# 64XkeySchem.net
KiCad netlist of a schematic drawn in Altium Designer
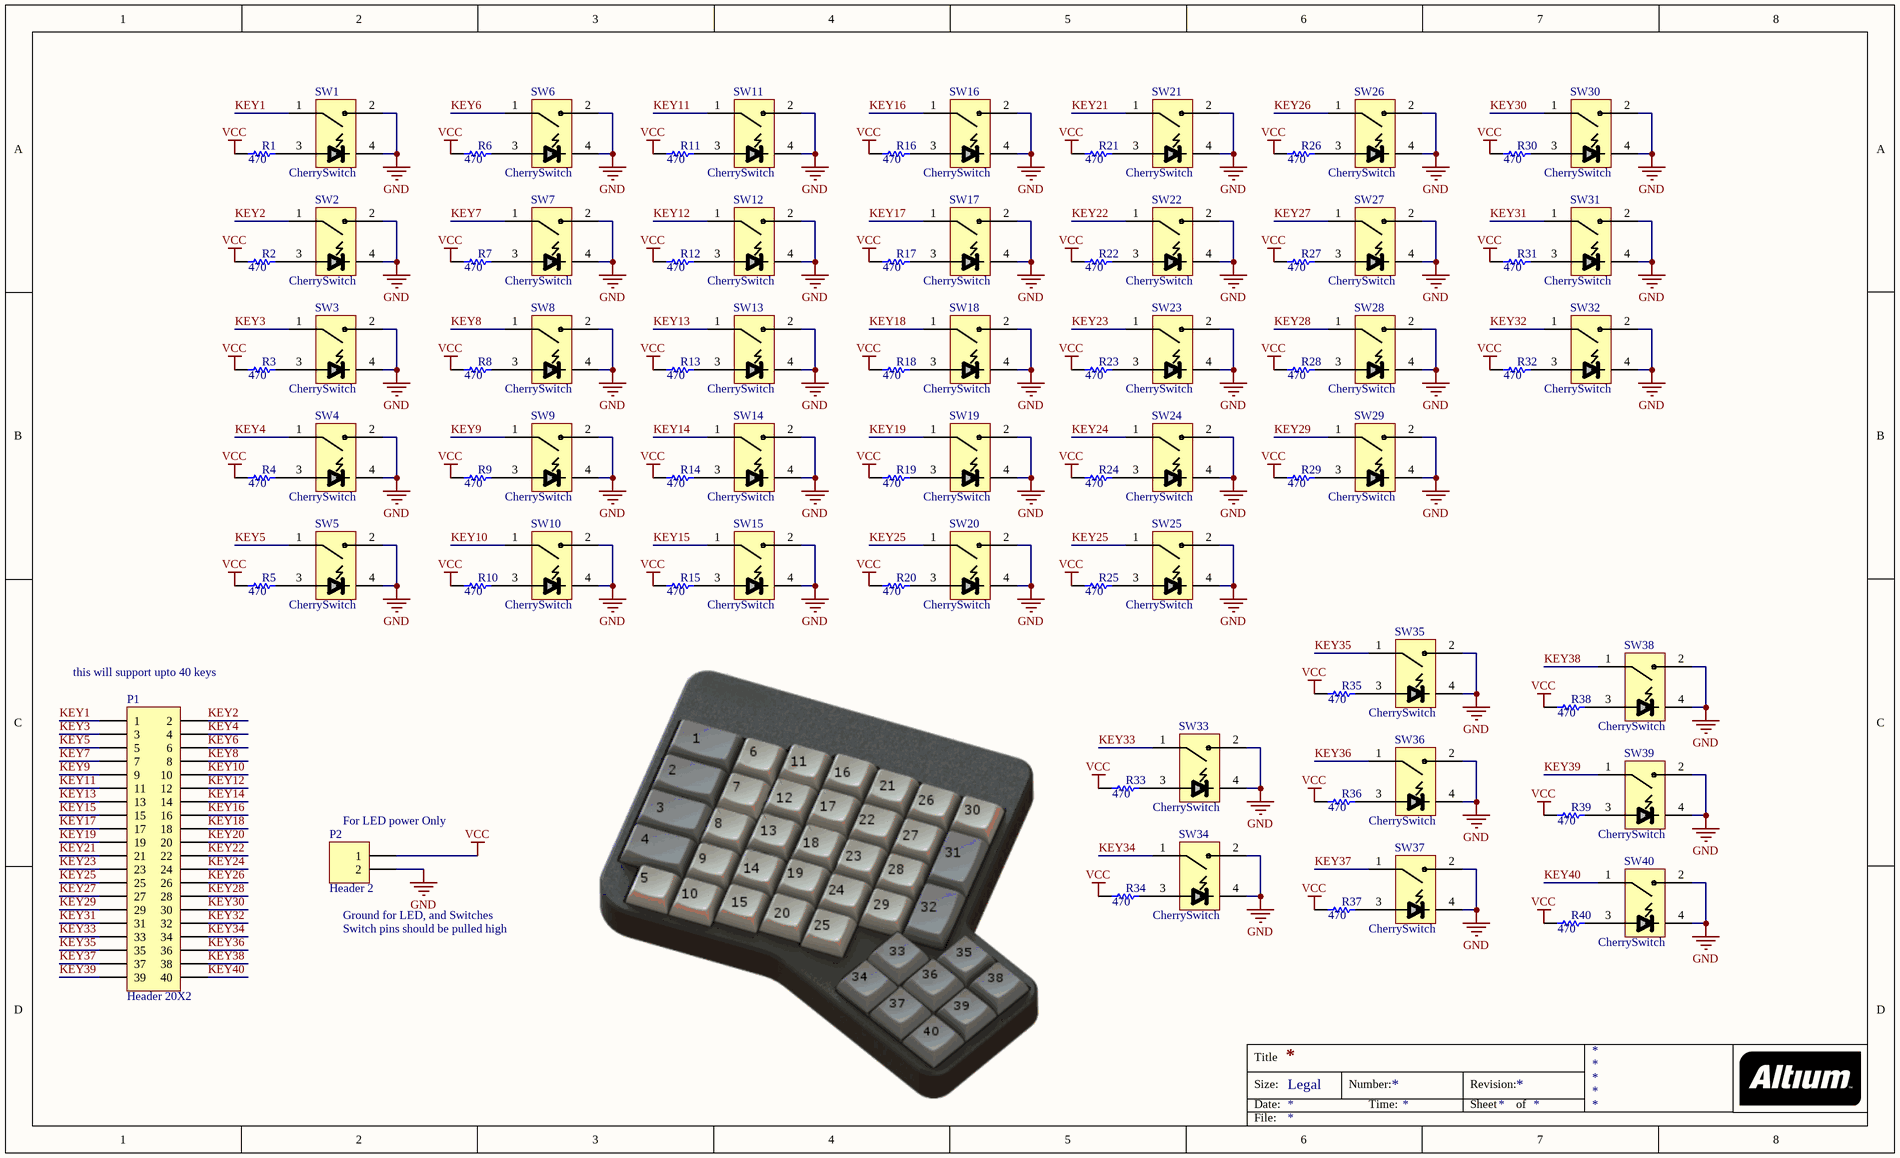
[diagram p0: 64XkeySchem.SchDoc]

(export (version "E")
  (design (tool "Eeschema 10.0.6"))
  (components
    (comp (ref "P1")
      (value "Header 20X2")
      (footprint "HDR2X20")
      (description "Header, 20-Pin, Dual row")
      (fields (field (name "PUBLISHER") "Altium Limited"))
      (libsource (lib "Miscellaneous Connectors") (part "Header 20X2"))
    )
    (comp (ref "P2")
      (value "Header 2")
      (footprint "HDR1X2")
      (description "Header, 2-Pin")
      (fields (field (name "PUBLISHER") "Altium Limited"))
      (libsource (lib "Miscellaneous Connectors") (part "Header 2"))
    )
    (comp (ref "R1")
      (value "470")
      (footprint "6-0805_N")
      (description "Semiconductor Resistor")
      (fields (field (name "Comment") "Res Semi") (field (name "PUBLISHER") "Altium Limited"))
      (libsource (lib "Miscellaneous Devices") (part "Res Semi"))
    )
    (comp (ref "R2")
      (value "470")
      (footprint "6-0805_N")
      (description "Semiconductor Resistor")
      (fields (field (name "Comment") "Res Semi") (field (name "PUBLISHER") "Altium Limited"))
      (libsource (lib "Miscellaneous Devices") (part "Res Semi"))
    )
    (comp (ref "R3")
      (value "470")
      (footprint "6-0805_N")
      (description "Semiconductor Resistor")
      (fields (field (name "Comment") "Res Semi") (field (name "PUBLISHER") "Altium Limited"))
      (libsource (lib "Miscellaneous Devices") (part "Res Semi"))
    )
    (comp (ref "R4")
      (value "470")
      (footprint "6-0805_N")
      (description "Semiconductor Resistor")
      (fields (field (name "Comment") "Res Semi") (field (name "PUBLISHER") "Altium Limited"))
      (libsource (lib "Miscellaneous Devices") (part "Res Semi"))
    )
    (comp (ref "R5")
      (value "470")
      (footprint "6-0805_N")
      (description "Semiconductor Resistor")
      (fields (field (name "Comment") "Res Semi") (field (name "PUBLISHER") "Altium Limited"))
      (libsource (lib "Miscellaneous Devices") (part "Res Semi"))
    )
    (comp (ref "R6")
      (value "470")
      (footprint "6-0805_N")
      (description "Semiconductor Resistor")
      (fields (field (name "Comment") "Res Semi") (field (name "PUBLISHER") "Altium Limited"))
      (libsource (lib "Miscellaneous Devices") (part "Res Semi"))
    )
    (comp (ref "R7")
      (value "470")
      (footprint "6-0805_N")
      (description "Semiconductor Resistor")
      (fields (field (name "Comment") "Res Semi") (field (name "PUBLISHER") "Altium Limited"))
      (libsource (lib "Miscellaneous Devices") (part "Res Semi"))
    )
    (comp (ref "R8")
      (value "470")
      (footprint "6-0805_N")
      (description "Semiconductor Resistor")
      (fields (field (name "Comment") "Res Semi") (field (name "PUBLISHER") "Altium Limited"))
      (libsource (lib "Miscellaneous Devices") (part "Res Semi"))
    )
    (comp (ref "R9")
      (value "470")
      (footprint "6-0805_N")
      (description "Semiconductor Resistor")
      (fields (field (name "Comment") "Res Semi") (field (name "PUBLISHER") "Altium Limited"))
      (libsource (lib "Miscellaneous Devices") (part "Res Semi"))
    )
    (comp (ref "R10")
      (value "470")
      (footprint "6-0805_N")
      (description "Semiconductor Resistor")
      (fields (field (name "Comment") "Res Semi") (field (name "PUBLISHER") "Altium Limited"))
      (libsource (lib "Miscellaneous Devices") (part "Res Semi"))
    )
    (comp (ref "R11")
      (value "470")
      (footprint "6-0805_N")
      (description "Semiconductor Resistor")
      (fields (field (name "Comment") "Res Semi") (field (name "PUBLISHER") "Altium Limited"))
      (libsource (lib "Miscellaneous Devices") (part "Res Semi"))
    )
    (comp (ref "R12")
      (value "470")
      (footprint "6-0805_N")
      (description "Semiconductor Resistor")
      (fields (field (name "Comment") "Res Semi") (field (name "PUBLISHER") "Altium Limited"))
      (libsource (lib "Miscellaneous Devices") (part "Res Semi"))
    )
    (comp (ref "R13")
      (value "470")
      (footprint "6-0805_N")
      (description "Semiconductor Resistor")
      (fields (field (name "Comment") "Res Semi") (field (name "PUBLISHER") "Altium Limited"))
      (libsource (lib "Miscellaneous Devices") (part "Res Semi"))
    )
    (comp (ref "R14")
      (value "470")
      (footprint "6-0805_N")
      (description "Semiconductor Resistor")
      (fields (field (name "Comment") "Res Semi") (field (name "PUBLISHER") "Altium Limited"))
      (libsource (lib "Miscellaneous Devices") (part "Res Semi"))
    )
    (comp (ref "R15")
      (value "470")
      (footprint "6-0805_N")
      (description "Semiconductor Resistor")
      (fields (field (name "Comment") "Res Semi") (field (name "PUBLISHER") "Altium Limited"))
      (libsource (lib "Miscellaneous Devices") (part "Res Semi"))
    )
    (comp (ref "R16")
      (value "470")
      (footprint "6-0805_N")
      (description "Semiconductor Resistor")
      (fields (field (name "Comment") "Res Semi") (field (name "PUBLISHER") "Altium Limited"))
      (libsource (lib "Miscellaneous Devices") (part "Res Semi"))
    )
    (comp (ref "R17")
      (value "470")
      (footprint "6-0805_N")
      (description "Semiconductor Resistor")
      (fields (field (name "Comment") "Res Semi") (field (name "PUBLISHER") "Altium Limited"))
      (libsource (lib "Miscellaneous Devices") (part "Res Semi"))
    )
    (comp (ref "R18")
      (value "470")
      (footprint "6-0805_N")
      (description "Semiconductor Resistor")
      (fields (field (name "Comment") "Res Semi") (field (name "PUBLISHER") "Altium Limited"))
      (libsource (lib "Miscellaneous Devices") (part "Res Semi"))
    )
    (comp (ref "R19")
      (value "470")
      (footprint "6-0805_N")
      (description "Semiconductor Resistor")
      (fields (field (name "Comment") "Res Semi") (field (name "PUBLISHER") "Altium Limited"))
      (libsource (lib "Miscellaneous Devices") (part "Res Semi"))
    )
    (comp (ref "R20")
      (value "470")
      (footprint "6-0805_N")
      (description "Semiconductor Resistor")
      (fields (field (name "Comment") "Res Semi") (field (name "PUBLISHER") "Altium Limited"))
      (libsource (lib "Miscellaneous Devices") (part "Res Semi"))
    )
    (comp (ref "R21")
      (value "470")
      (footprint "6-0805_N")
      (description "Semiconductor Resistor")
      (fields (field (name "Comment") "Res Semi") (field (name "PUBLISHER") "Altium Limited"))
      (libsource (lib "Miscellaneous Devices") (part "Res Semi"))
    )
    (comp (ref "R22")
      (value "470")
      (footprint "6-0805_N")
      (description "Semiconductor Resistor")
      (fields (field (name "Comment") "Res Semi") (field (name "PUBLISHER") "Altium Limited"))
      (libsource (lib "Miscellaneous Devices") (part "Res Semi"))
    )
    (comp (ref "R23")
      (value "470")
      (footprint "6-0805_N")
      (description "Semiconductor Resistor")
      (fields (field (name "Comment") "Res Semi") (field (name "PUBLISHER") "Altium Limited"))
      (libsource (lib "Miscellaneous Devices") (part "Res Semi"))
    )
    (comp (ref "R24")
      (value "470")
      (footprint "6-0805_N")
      (description "Semiconductor Resistor")
      (fields (field (name "Comment") "Res Semi") (field (name "PUBLISHER") "Altium Limited"))
      (libsource (lib "Miscellaneous Devices") (part "Res Semi"))
    )
    (comp (ref "R25")
      (value "470")
      (footprint "6-0805_N")
      (description "Semiconductor Resistor")
      (fields (field (name "Comment") "Res Semi") (field (name "PUBLISHER") "Altium Limited"))
      (libsource (lib "Miscellaneous Devices") (part "Res Semi"))
    )
    (comp (ref "R26")
      (value "470")
      (footprint "6-0805_N")
      (description "Semiconductor Resistor")
      (fields (field (name "Comment") "Res Semi") (field (name "PUBLISHER") "Altium Limited"))
      (libsource (lib "Miscellaneous Devices") (part "Res Semi"))
    )
    (comp (ref "R27")
      (value "470")
      (footprint "6-0805_N")
      (description "Semiconductor Resistor")
      (fields (field (name "Comment") "Res Semi") (field (name "PUBLISHER") "Altium Limited"))
      (libsource (lib "Miscellaneous Devices") (part "Res Semi"))
    )
    (comp (ref "R28")
      (value "470")
      (footprint "6-0805_N")
      (description "Semiconductor Resistor")
      (fields (field (name "Comment") "Res Semi") (field (name "PUBLISHER") "Altium Limited"))
      (libsource (lib "Miscellaneous Devices") (part "Res Semi"))
    )
    (comp (ref "R29")
      (value "470")
      (footprint "6-0805_N")
      (description "Semiconductor Resistor")
      (fields (field (name "Comment") "Res Semi") (field (name "PUBLISHER") "Altium Limited"))
      (libsource (lib "Miscellaneous Devices") (part "Res Semi"))
    )
    (comp (ref "R30")
      (value "470")
      (footprint "6-0805_N")
      (description "Semiconductor Resistor")
      (fields (field (name "Comment") "Res Semi") (field (name "PUBLISHER") "Altium Limited"))
      (libsource (lib "Miscellaneous Devices") (part "Res Semi"))
    )
    (comp (ref "R31")
      (value "470")
      (footprint "6-0805_N")
      (description "Semiconductor Resistor")
      (fields (field (name "Comment") "Res Semi") (field (name "PUBLISHER") "Altium Limited"))
      (libsource (lib "Miscellaneous Devices") (part "Res Semi"))
    )
    (comp (ref "R32")
      (value "470")
      (footprint "6-0805_N")
      (description "Semiconductor Resistor")
      (fields (field (name "Comment") "Res Semi") (field (name "PUBLISHER") "Altium Limited"))
      (libsource (lib "Miscellaneous Devices") (part "Res Semi"))
    )
    (comp (ref "R33")
      (value "470")
      (footprint "6-0805_N")
      (description "Semiconductor Resistor")
      (fields (field (name "Comment") "Res Semi") (field (name "PUBLISHER") "Altium Limited"))
      (libsource (lib "Miscellaneous Devices") (part "Res Semi"))
    )
    (comp (ref "R34")
      (value "470")
      (footprint "6-0805_N")
      (description "Semiconductor Resistor")
      (fields (field (name "Comment") "Res Semi") (field (name "PUBLISHER") "Altium Limited"))
      (libsource (lib "Miscellaneous Devices") (part "Res Semi"))
    )
    (comp (ref "R35")
      (value "470")
      (footprint "6-0805_N")
      (description "Semiconductor Resistor")
      (fields (field (name "Comment") "Res Semi") (field (name "PUBLISHER") "Altium Limited"))
      (libsource (lib "Miscellaneous Devices") (part "Res Semi"))
    )
    (comp (ref "R36")
      (value "470")
      (footprint "6-0805_N")
      (description "Semiconductor Resistor")
      (fields (field (name "Comment") "Res Semi") (field (name "PUBLISHER") "Altium Limited"))
      (libsource (lib "Miscellaneous Devices") (part "Res Semi"))
    )
    (comp (ref "R37")
      (value "470")
      (footprint "6-0805_N")
      (description "Semiconductor Resistor")
      (fields (field (name "Comment") "Res Semi") (field (name "PUBLISHER") "Altium Limited"))
      (libsource (lib "Miscellaneous Devices") (part "Res Semi"))
    )
    (comp (ref "R38")
      (value "470")
      (footprint "6-0805_N")
      (description "Semiconductor Resistor")
      (fields (field (name "Comment") "Res Semi") (field (name "PUBLISHER") "Altium Limited"))
      (libsource (lib "Miscellaneous Devices") (part "Res Semi"))
    )
    (comp (ref "R39")
      (value "470")
      (footprint "6-0805_N")
      (description "Semiconductor Resistor")
      (fields (field (name "Comment") "Res Semi") (field (name "PUBLISHER") "Altium Limited"))
      (libsource (lib "Miscellaneous Devices") (part "Res Semi"))
    )
    (comp (ref "R40")
      (value "470")
      (footprint "6-0805_N")
      (description "Semiconductor Resistor")
      (fields (field (name "Comment") "Res Semi") (field (name "PUBLISHER") "Altium Limited"))
      (libsource (lib "Miscellaneous Devices") (part "Res Semi"))
    )
    (comp (ref "SW1")
      (value "CherrySwitch")
      (footprint "CherryMxSwitch")
      (description "Cherry MX Switch layout")
      (libsource (lib "mainBoardLib") (part "CherrySwitch"))
    )
    (comp (ref "SW2")
      (value "CherrySwitch")
      (footprint "CherryMxSwitch")
      (description "Cherry MX Switch layout")
      (libsource (lib "mainBoardLib") (part "CherrySwitch"))
    )
    (comp (ref "SW3")
      (value "CherrySwitch")
      (footprint "CherryMxSwitch")
      (description "Cherry MX Switch layout")
      (libsource (lib "mainBoardLib") (part "CherrySwitch"))
    )
    (comp (ref "SW4")
      (value "CherrySwitch")
      (footprint "CherryMxSwitch")
      (description "Cherry MX Switch layout")
      (libsource (lib "mainBoardLib") (part "CherrySwitch"))
    )
    (comp (ref "SW5")
      (value "CherrySwitch")
      (footprint "CherryMxSwitch")
      (description "Cherry MX Switch layout")
      (libsource (lib "mainBoardLib") (part "CherrySwitch"))
    )
    (comp (ref "SW6")
      (value "CherrySwitch")
      (footprint "CherryMxSwitch")
      (description "Cherry MX Switch layout")
      (libsource (lib "mainBoardLib") (part "CherrySwitch"))
    )
    (comp (ref "SW7")
      (value "CherrySwitch")
      (footprint "CherryMxSwitch")
      (description "Cherry MX Switch layout")
      (libsource (lib "mainBoardLib") (part "CherrySwitch"))
    )
    (comp (ref "SW8")
      (value "CherrySwitch")
      (footprint "CherryMxSwitch")
      (description "Cherry MX Switch layout")
      (libsource (lib "mainBoardLib") (part "CherrySwitch"))
    )
    (comp (ref "SW9")
      (value "CherrySwitch")
      (footprint "CherryMxSwitch")
      (description "Cherry MX Switch layout")
      (libsource (lib "mainBoardLib") (part "CherrySwitch"))
    )
    (comp (ref "SW10")
      (value "CherrySwitch")
      (footprint "CherryMxSwitch")
      (description "Cherry MX Switch layout")
      (libsource (lib "mainBoardLib") (part "CherrySwitch"))
    )
    (comp (ref "SW11")
      (value "CherrySwitch")
      (footprint "CherryMxSwitch")
      (description "Cherry MX Switch layout")
      (libsource (lib "mainBoardLib") (part "CherrySwitch"))
    )
    (comp (ref "SW12")
      (value "CherrySwitch")
      (footprint "CherryMxSwitch")
      (description "Cherry MX Switch layout")
      (libsource (lib "mainBoardLib") (part "CherrySwitch"))
    )
    (comp (ref "SW13")
      (value "CherrySwitch")
      (footprint "CherryMxSwitch")
      (description "Cherry MX Switch layout")
      (libsource (lib "mainBoardLib") (part "CherrySwitch"))
    )
    (comp (ref "SW14")
      (value "CherrySwitch")
      (footprint "CherryMxSwitch")
      (description "Cherry MX Switch layout")
      (libsource (lib "mainBoardLib") (part "CherrySwitch"))
    )
    (comp (ref "SW15")
      (value "CherrySwitch")
      (footprint "CherryMxSwitch")
      (description "Cherry MX Switch layout")
      (libsource (lib "mainBoardLib") (part "CherrySwitch"))
    )
    (comp (ref "SW16")
      (value "CherrySwitch")
      (footprint "CherryMxSwitch")
      (description "Cherry MX Switch layout")
      (libsource (lib "mainBoardLib") (part "CherrySwitch"))
    )
    (comp (ref "SW17")
      (value "CherrySwitch")
      (footprint "CherryMxSwitch")
      (description "Cherry MX Switch layout")
      (libsource (lib "mainBoardLib") (part "CherrySwitch"))
    )
    (comp (ref "SW18")
      (value "CherrySwitch")
      (footprint "CherryMxSwitch")
      (description "Cherry MX Switch layout")
      (libsource (lib "mainBoardLib") (part "CherrySwitch"))
    )
    (comp (ref "SW19")
      (value "CherrySwitch")
      (footprint "CherryMxSwitch")
      (description "Cherry MX Switch layout")
      (libsource (lib "mainBoardLib") (part "CherrySwitch"))
    )
    (comp (ref "SW20")
      (value "CherrySwitch")
      (footprint "CherryMxSwitch")
      (description "Cherry MX Switch layout")
      (libsource (lib "mainBoardLib") (part "CherrySwitch"))
    )
    (comp (ref "SW21")
      (value "CherrySwitch")
      (footprint "CherryMxSwitch")
      (description "Cherry MX Switch layout")
      (libsource (lib "mainBoardLib") (part "CherrySwitch"))
    )
    (comp (ref "SW22")
      (value "CherrySwitch")
      (footprint "CherryMxSwitch")
      (description "Cherry MX Switch layout")
      (libsource (lib "mainBoardLib") (part "CherrySwitch"))
    )
    (comp (ref "SW23")
      (value "CherrySwitch")
      (footprint "CherryMxSwitch")
      (description "Cherry MX Switch layout")
      (libsource (lib "mainBoardLib") (part "CherrySwitch"))
    )
    (comp (ref "SW24")
      (value "CherrySwitch")
      (footprint "CherryMxSwitch")
      (description "Cherry MX Switch layout")
      (libsource (lib "mainBoardLib") (part "CherrySwitch"))
    )
    (comp (ref "SW25")
      (value "CherrySwitch")
      (footprint "CherryMxSwitch")
      (description "Cherry MX Switch layout")
      (libsource (lib "mainBoardLib") (part "CherrySwitch"))
    )
    (comp (ref "SW26")
      (value "CherrySwitch")
      (footprint "CherryMxSwitch")
      (description "Cherry MX Switch layout")
      (libsource (lib "mainBoardLib") (part "CherrySwitch"))
    )
    (comp (ref "SW27")
      (value "CherrySwitch")
      (footprint "CherryMxSwitch")
      (description "Cherry MX Switch layout")
      (libsource (lib "mainBoardLib") (part "CherrySwitch"))
    )
    (comp (ref "SW28")
      (value "CherrySwitch")
      (footprint "CherryMxSwitch")
      (description "Cherry MX Switch layout")
      (libsource (lib "mainBoardLib") (part "CherrySwitch"))
    )
    (comp (ref "SW29")
      (value "CherrySwitch")
      (footprint "CherryMxSwitch")
      (description "Cherry MX Switch layout")
      (libsource (lib "mainBoardLib") (part "CherrySwitch"))
    )
    (comp (ref "SW30")
      (value "CherrySwitch")
      (footprint "CherryMxSwitch")
      (description "Cherry MX Switch layout")
      (libsource (lib "mainBoardLib") (part "CherrySwitch"))
    )
    (comp (ref "SW31")
      (value "CherrySwitch")
      (footprint "CherryMxSwitch")
      (description "Cherry MX Switch layout")
      (libsource (lib "mainBoardLib") (part "CherrySwitch"))
    )
    (comp (ref "SW32")
      (value "CherrySwitch")
      (footprint "CherryMxSwitch")
      (description "Cherry MX Switch layout")
      (libsource (lib "mainBoardLib") (part "CherrySwitch"))
    )
    (comp (ref "SW33")
      (value "CherrySwitch")
      (footprint "CherryMxSwitch")
      (description "Cherry MX Switch layout")
      (libsource (lib "mainBoardLib") (part "CherrySwitch"))
    )
    (comp (ref "SW34")
      (value "CherrySwitch")
      (footprint "CherryMxSwitch")
      (description "Cherry MX Switch layout")
      (libsource (lib "mainBoardLib") (part "CherrySwitch"))
    )
    (comp (ref "SW35")
      (value "CherrySwitch")
      (footprint "CherryMxSwitch")
      (description "Cherry MX Switch layout")
      (libsource (lib "mainBoardLib") (part "CherrySwitch"))
    )
    (comp (ref "SW36")
      (value "CherrySwitch")
      (footprint "CherryMxSwitch")
      (description "Cherry MX Switch layout")
      (libsource (lib "mainBoardLib") (part "CherrySwitch"))
    )
    (comp (ref "SW37")
      (value "CherrySwitch")
      (footprint "CherryMxSwitch")
      (description "Cherry MX Switch layout")
      (libsource (lib "mainBoardLib") (part "CherrySwitch"))
    )
    (comp (ref "SW38")
      (value "CherrySwitch")
      (footprint "CherryMxSwitch")
      (description "Cherry MX Switch layout")
      (libsource (lib "mainBoardLib") (part "CherrySwitch"))
    )
    (comp (ref "SW39")
      (value "CherrySwitch")
      (footprint "CherryMxSwitch")
      (description "Cherry MX Switch layout")
      (libsource (lib "mainBoardLib") (part "CherrySwitch"))
    )
    (comp (ref "SW40")
      (value "CherrySwitch")
      (footprint "CherryMxSwitch")
      (description "Cherry MX Switch layout")
      (libsource (lib "mainBoardLib") (part "CherrySwitch"))
    )
  )
  (nets
    (net (code "1") (name "/KEY1") (class "Default")
      (node (ref "P1") (pin "1") (pinfunction "1_1") (pintype "passive"))
      (node (ref "SW1") (pin "1") (pinfunction "1_1") (pintype "passive"))
    )
    (net (code "2") (name "/KEY2") (class "Default")
      (node (ref "P1") (pin "2") (pinfunction "2_2") (pintype "passive"))
      (node (ref "SW2") (pin "1") (pinfunction "1_1") (pintype "passive"))
    )
    (net (code "3") (name "/KEY3") (class "Default")
      (node (ref "P1") (pin "3") (pinfunction "3_3") (pintype "passive"))
      (node (ref "SW3") (pin "1") (pinfunction "1_1") (pintype "passive"))
    )
    (net (code "4") (name "/KEY4") (class "Default")
      (node (ref "P1") (pin "4") (pinfunction "4_4") (pintype "passive"))
      (node (ref "SW4") (pin "1") (pinfunction "1_1") (pintype "passive"))
    )
    (net (code "5") (name "/KEY5") (class "Default")
      (node (ref "P1") (pin "5") (pinfunction "5_5") (pintype "passive"))
      (node (ref "SW5") (pin "1") (pinfunction "1_1") (pintype "passive"))
    )
    (net (code "6") (name "/KEY6") (class "Default")
      (node (ref "P1") (pin "6") (pinfunction "6_6") (pintype "passive"))
      (node (ref "SW6") (pin "1") (pinfunction "1_1") (pintype "passive"))
    )
    (net (code "7") (name "/KEY7") (class "Default")
      (node (ref "P1") (pin "7") (pinfunction "7_7") (pintype "passive"))
      (node (ref "SW7") (pin "1") (pinfunction "1_1") (pintype "passive"))
    )
    (net (code "8") (name "/KEY8") (class "Default")
      (node (ref "P1") (pin "8") (pinfunction "8_8") (pintype "passive"))
      (node (ref "SW8") (pin "1") (pinfunction "1_1") (pintype "passive"))
    )
    (net (code "9") (name "/KEY9") (class "Default")
      (node (ref "P1") (pin "9") (pinfunction "9_9") (pintype "passive"))
      (node (ref "SW9") (pin "1") (pinfunction "1_1") (pintype "passive"))
    )
    (net (code "10") (name "/KEY10") (class "Default")
      (node (ref "P1") (pin "10") (pinfunction "10_10") (pintype "passive"))
      (node (ref "SW10") (pin "1") (pinfunction "1_1") (pintype "passive"))
    )
    (net (code "11") (name "/KEY11") (class "Default")
      (node (ref "P1") (pin "11") (pinfunction "11_11") (pintype "passive"))
      (node (ref "SW11") (pin "1") (pinfunction "1_1") (pintype "passive"))
    )
    (net (code "12") (name "/KEY12") (class "Default")
      (node (ref "P1") (pin "12") (pinfunction "12_12") (pintype "passive"))
      (node (ref "SW12") (pin "1") (pinfunction "1_1") (pintype "passive"))
    )
    (net (code "13") (name "/KEY13") (class "Default")
      (node (ref "P1") (pin "13") (pinfunction "13_13") (pintype "passive"))
      (node (ref "SW13") (pin "1") (pinfunction "1_1") (pintype "passive"))
    )
    (net (code "14") (name "/KEY14") (class "Default")
      (node (ref "P1") (pin "14") (pinfunction "14_14") (pintype "passive"))
      (node (ref "SW14") (pin "1") (pinfunction "1_1") (pintype "passive"))
    )
    (net (code "15") (name "/KEY15") (class "Default")
      (node (ref "P1") (pin "15") (pinfunction "15_15") (pintype "passive"))
      (node (ref "SW15") (pin "1") (pinfunction "1_1") (pintype "passive"))
    )
    (net (code "16") (name "/KEY16") (class "Default")
      (node (ref "P1") (pin "16") (pinfunction "16_16") (pintype "passive"))
      (node (ref "SW16") (pin "1") (pinfunction "1_1") (pintype "passive"))
    )
    (net (code "17") (name "/KEY17") (class "Default")
      (node (ref "P1") (pin "17") (pinfunction "17_17") (pintype "passive"))
      (node (ref "SW17") (pin "1") (pinfunction "1_1") (pintype "passive"))
    )
    (net (code "18") (name "/KEY18") (class "Default")
      (node (ref "P1") (pin "18") (pinfunction "18_18") (pintype "passive"))
      (node (ref "SW18") (pin "1") (pinfunction "1_1") (pintype "passive"))
    )
    (net (code "19") (name "/KEY19") (class "Default")
      (node (ref "P1") (pin "19") (pinfunction "19_19") (pintype "passive"))
      (node (ref "SW19") (pin "1") (pinfunction "1_1") (pintype "passive"))
    )
    (net (code "20") (name "/KEY20") (class "Default")
      (node (ref "P1") (pin "20") (pinfunction "20_20") (pintype "passive"))
    )
    (net (code "21") (name "/KEY21") (class "Default")
      (node (ref "P1") (pin "21") (pinfunction "21_21") (pintype "passive"))
      (node (ref "SW21") (pin "1") (pinfunction "1_1") (pintype "passive"))
    )
    (net (code "22") (name "/KEY22") (class "Default")
      (node (ref "P1") (pin "22") (pinfunction "22_22") (pintype "passive"))
      (node (ref "SW22") (pin "1") (pinfunction "1_1") (pintype "passive"))
    )
    (net (code "23") (name "/KEY23") (class "Default")
      (node (ref "P1") (pin "23") (pinfunction "23_23") (pintype "passive"))
      (node (ref "SW23") (pin "1") (pinfunction "1_1") (pintype "passive"))
    )
    (net (code "24") (name "/KEY24") (class "Default")
      (node (ref "P1") (pin "24") (pinfunction "24_24") (pintype "passive"))
      (node (ref "SW24") (pin "1") (pinfunction "1_1") (pintype "passive"))
    )
    (net (code "25") (name "/KEY25") (class "Default")
      (node (ref "P1") (pin "25") (pinfunction "25_25") (pintype "passive"))
      (node (ref "SW20") (pin "1") (pinfunction "1_1") (pintype "passive"))
      (node (ref "SW25") (pin "1") (pinfunction "1_1") (pintype "passive"))
    )
    (net (code "26") (name "/KEY26") (class "Default")
      (node (ref "P1") (pin "26") (pinfunction "26_26") (pintype "passive"))
      (node (ref "SW26") (pin "1") (pinfunction "1_1") (pintype "passive"))
    )
    (net (code "27") (name "/KEY27") (class "Default")
      (node (ref "P1") (pin "27") (pinfunction "27_27") (pintype "passive"))
      (node (ref "SW27") (pin "1") (pinfunction "1_1") (pintype "passive"))
    )
    (net (code "28") (name "/KEY28") (class "Default")
      (node (ref "P1") (pin "28") (pinfunction "28_28") (pintype "passive"))
      (node (ref "SW28") (pin "1") (pinfunction "1_1") (pintype "passive"))
    )
    (net (code "29") (name "/KEY29") (class "Default")
      (node (ref "P1") (pin "29") (pinfunction "29_29") (pintype "passive"))
      (node (ref "SW29") (pin "1") (pinfunction "1_1") (pintype "passive"))
    )
    (net (code "30") (name "/KEY30") (class "Default")
      (node (ref "P1") (pin "30") (pinfunction "30_30") (pintype "passive"))
      (node (ref "SW30") (pin "1") (pinfunction "1_1") (pintype "passive"))
    )
    (net (code "31") (name "/KEY31") (class "Default")
      (node (ref "P1") (pin "31") (pinfunction "31_31") (pintype "passive"))
      (node (ref "SW31") (pin "1") (pinfunction "1_1") (pintype "passive"))
    )
    (net (code "32") (name "/KEY32") (class "Default")
      (node (ref "P1") (pin "32") (pinfunction "32_32") (pintype "passive"))
      (node (ref "SW32") (pin "1") (pinfunction "1_1") (pintype "passive"))
    )
    (net (code "33") (name "/KEY33") (class "Default")
      (node (ref "P1") (pin "33") (pinfunction "33_33") (pintype "passive"))
      (node (ref "SW33") (pin "1") (pinfunction "1_1") (pintype "passive"))
    )
    (net (code "34") (name "/KEY34") (class "Default")
      (node (ref "P1") (pin "34") (pinfunction "34_34") (pintype "passive"))
      (node (ref "SW34") (pin "1") (pinfunction "1_1") (pintype "passive"))
    )
    (net (code "35") (name "/KEY35") (class "Default")
      (node (ref "P1") (pin "35") (pinfunction "35_35") (pintype "passive"))
      (node (ref "SW35") (pin "1") (pinfunction "1_1") (pintype "passive"))
    )
    (net (code "36") (name "/KEY36") (class "Default")
      (node (ref "P1") (pin "36") (pinfunction "36_36") (pintype "passive"))
      (node (ref "SW36") (pin "1") (pinfunction "1_1") (pintype "passive"))
    )
    (net (code "37") (name "/KEY37") (class "Default")
      (node (ref "P1") (pin "37") (pinfunction "37_37") (pintype "passive"))
      (node (ref "SW37") (pin "1") (pinfunction "1_1") (pintype "passive"))
    )
    (net (code "38") (name "/KEY38") (class "Default")
      (node (ref "P1") (pin "38") (pinfunction "38_38") (pintype "passive"))
      (node (ref "SW38") (pin "1") (pinfunction "1_1") (pintype "passive"))
    )
    (net (code "39") (name "/KEY39") (class "Default")
      (node (ref "P1") (pin "39") (pinfunction "39_39") (pintype "passive"))
      (node (ref "SW39") (pin "1") (pinfunction "1_1") (pintype "passive"))
    )
    (net (code "40") (name "/KEY40") (class "Default")
      (node (ref "P1") (pin "40") (pinfunction "40_40") (pintype "passive"))
      (node (ref "SW40") (pin "1") (pinfunction "1_1") (pintype "passive"))
    )
    (net (code "41") (name "GND") (class "Default")
      (node (ref "P2") (pin "2") (pinfunction "2_2") (pintype "passive"))
      (node (ref "SW1") (pin "2") (pinfunction "2_2") (pintype "passive"))
      (node (ref "SW1") (pin "4") (pinfunction "4_4") (pintype "passive"))
      (node (ref "SW10") (pin "2") (pinfunction "2_2") (pintype "passive"))
      (node (ref "SW10") (pin "4") (pinfunction "4_4") (pintype "passive"))
      (node (ref "SW11") (pin "2") (pinfunction "2_2") (pintype "passive"))
      (node (ref "SW11") (pin "4") (pinfunction "4_4") (pintype "passive"))
      (node (ref "SW12") (pin "2") (pinfunction "2_2") (pintype "passive"))
      (node (ref "SW12") (pin "4") (pinfunction "4_4") (pintype "passive"))
      (node (ref "SW13") (pin "2") (pinfunction "2_2") (pintype "passive"))
      (node (ref "SW13") (pin "4") (pinfunction "4_4") (pintype "passive"))
      (node (ref "SW14") (pin "2") (pinfunction "2_2") (pintype "passive"))
      (node (ref "SW14") (pin "4") (pinfunction "4_4") (pintype "passive"))
      (node (ref "SW15") (pin "2") (pinfunction "2_2") (pintype "passive"))
      (node (ref "SW15") (pin "4") (pinfunction "4_4") (pintype "passive"))
      (node (ref "SW16") (pin "2") (pinfunction "2_2") (pintype "passive"))
      (node (ref "SW16") (pin "4") (pinfunction "4_4") (pintype "passive"))
      (node (ref "SW17") (pin "2") (pinfunction "2_2") (pintype "passive"))
      (node (ref "SW17") (pin "4") (pinfunction "4_4") (pintype "passive"))
      (node (ref "SW18") (pin "2") (pinfunction "2_2") (pintype "passive"))
      (node (ref "SW18") (pin "4") (pinfunction "4_4") (pintype "passive"))
      (node (ref "SW19") (pin "2") (pinfunction "2_2") (pintype "passive"))
      (node (ref "SW19") (pin "4") (pinfunction "4_4") (pintype "passive"))
      (node (ref "SW2") (pin "2") (pinfunction "2_2") (pintype "passive"))
      (node (ref "SW2") (pin "4") (pinfunction "4_4") (pintype "passive"))
      (node (ref "SW20") (pin "2") (pinfunction "2_2") (pintype "passive"))
      (node (ref "SW20") (pin "4") (pinfunction "4_4") (pintype "passive"))
      (node (ref "SW21") (pin "2") (pinfunction "2_2") (pintype "passive"))
      (node (ref "SW21") (pin "4") (pinfunction "4_4") (pintype "passive"))
      (node (ref "SW22") (pin "2") (pinfunction "2_2") (pintype "passive"))
      (node (ref "SW22") (pin "4") (pinfunction "4_4") (pintype "passive"))
      (node (ref "SW23") (pin "2") (pinfunction "2_2") (pintype "passive"))
      (node (ref "SW23") (pin "4") (pinfunction "4_4") (pintype "passive"))
      (node (ref "SW24") (pin "2") (pinfunction "2_2") (pintype "passive"))
      (node (ref "SW24") (pin "4") (pinfunction "4_4") (pintype "passive"))
      (node (ref "SW25") (pin "2") (pinfunction "2_2") (pintype "passive"))
      (node (ref "SW25") (pin "4") (pinfunction "4_4") (pintype "passive"))
      (node (ref "SW26") (pin "2") (pinfunction "2_2") (pintype "passive"))
      (node (ref "SW26") (pin "4") (pinfunction "4_4") (pintype "passive"))
      (node (ref "SW27") (pin "2") (pinfunction "2_2") (pintype "passive"))
      (node (ref "SW27") (pin "4") (pinfunction "4_4") (pintype "passive"))
      (node (ref "SW28") (pin "2") (pinfunction "2_2") (pintype "passive"))
      (node (ref "SW28") (pin "4") (pinfunction "4_4") (pintype "passive"))
      (node (ref "SW29") (pin "2") (pinfunction "2_2") (pintype "passive"))
      (node (ref "SW29") (pin "4") (pinfunction "4_4") (pintype "passive"))
      (node (ref "SW3") (pin "2") (pinfunction "2_2") (pintype "passive"))
      (node (ref "SW3") (pin "4") (pinfunction "4_4") (pintype "passive"))
      (node (ref "SW30") (pin "2") (pinfunction "2_2") (pintype "passive"))
      (node (ref "SW30") (pin "4") (pinfunction "4_4") (pintype "passive"))
      (node (ref "SW31") (pin "2") (pinfunction "2_2") (pintype "passive"))
      (node (ref "SW31") (pin "4") (pinfunction "4_4") (pintype "passive"))
      (node (ref "SW32") (pin "2") (pinfunction "2_2") (pintype "passive"))
      (node (ref "SW32") (pin "4") (pinfunction "4_4") (pintype "passive"))
      (node (ref "SW33") (pin "2") (pinfunction "2_2") (pintype "passive"))
      (node (ref "SW33") (pin "4") (pinfunction "4_4") (pintype "passive"))
      (node (ref "SW34") (pin "2") (pinfunction "2_2") (pintype "passive"))
      (node (ref "SW34") (pin "4") (pinfunction "4_4") (pintype "passive"))
      (node (ref "SW35") (pin "2") (pinfunction "2_2") (pintype "passive"))
      (node (ref "SW35") (pin "4") (pinfunction "4_4") (pintype "passive"))
      (node (ref "SW36") (pin "2") (pinfunction "2_2") (pintype "passive"))
      (node (ref "SW36") (pin "4") (pinfunction "4_4") (pintype "passive"))
      (node (ref "SW37") (pin "2") (pinfunction "2_2") (pintype "passive"))
      (node (ref "SW37") (pin "4") (pinfunction "4_4") (pintype "passive"))
      (node (ref "SW38") (pin "2") (pinfunction "2_2") (pintype "passive"))
      (node (ref "SW38") (pin "4") (pinfunction "4_4") (pintype "passive"))
      (node (ref "SW39") (pin "2") (pinfunction "2_2") (pintype "passive"))
      (node (ref "SW39") (pin "4") (pinfunction "4_4") (pintype "passive"))
      (node (ref "SW4") (pin "2") (pinfunction "2_2") (pintype "passive"))
      (node (ref "SW4") (pin "4") (pinfunction "4_4") (pintype "passive"))
      (node (ref "SW40") (pin "2") (pinfunction "2_2") (pintype "passive"))
      (node (ref "SW40") (pin "4") (pinfunction "4_4") (pintype "passive"))
      (node (ref "SW5") (pin "2") (pinfunction "2_2") (pintype "passive"))
      (node (ref "SW5") (pin "4") (pinfunction "4_4") (pintype "passive"))
      (node (ref "SW6") (pin "2") (pinfunction "2_2") (pintype "passive"))
      (node (ref "SW6") (pin "4") (pinfunction "4_4") (pintype "passive"))
      (node (ref "SW7") (pin "2") (pinfunction "2_2") (pintype "passive"))
      (node (ref "SW7") (pin "4") (pinfunction "4_4") (pintype "passive"))
      (node (ref "SW8") (pin "2") (pinfunction "2_2") (pintype "passive"))
      (node (ref "SW8") (pin "4") (pinfunction "4_4") (pintype "passive"))
      (node (ref "SW9") (pin "2") (pinfunction "2_2") (pintype "passive"))
      (node (ref "SW9") (pin "4") (pinfunction "4_4") (pintype "passive"))
    )
    (net (code "42") (name "Net-(R1-Pad2)") (class "Default")
      (node (ref "R1") (pin "2") (pinfunction "2_2") (pintype "passive"))
      (node (ref "SW1") (pin "3") (pinfunction "3_3") (pintype "passive"))
    )
    (net (code "43") (name "Net-(R2-Pad2)") (class "Default")
      (node (ref "R2") (pin "2") (pinfunction "2_2") (pintype "passive"))
      (node (ref "SW2") (pin "3") (pinfunction "3_3") (pintype "passive"))
    )
    (net (code "44") (name "Net-(R3-Pad2)") (class "Default")
      (node (ref "R3") (pin "2") (pinfunction "2_2") (pintype "passive"))
      (node (ref "SW3") (pin "3") (pinfunction "3_3") (pintype "passive"))
    )
    (net (code "45") (name "Net-(R4-Pad2)") (class "Default")
      (node (ref "R4") (pin "2") (pinfunction "2_2") (pintype "passive"))
      (node (ref "SW4") (pin "3") (pinfunction "3_3") (pintype "passive"))
    )
    (net (code "46") (name "Net-(R5-Pad2)") (class "Default")
      (node (ref "R5") (pin "2") (pinfunction "2_2") (pintype "passive"))
      (node (ref "SW5") (pin "3") (pinfunction "3_3") (pintype "passive"))
    )
    (net (code "47") (name "Net-(R6-Pad2)") (class "Default")
      (node (ref "R6") (pin "2") (pinfunction "2_2") (pintype "passive"))
      (node (ref "SW6") (pin "3") (pinfunction "3_3") (pintype "passive"))
    )
    (net (code "48") (name "Net-(R7-Pad2)") (class "Default")
      (node (ref "R7") (pin "2") (pinfunction "2_2") (pintype "passive"))
      (node (ref "SW7") (pin "3") (pinfunction "3_3") (pintype "passive"))
    )
    (net (code "49") (name "Net-(R8-Pad2)") (class "Default")
      (node (ref "R8") (pin "2") (pinfunction "2_2") (pintype "passive"))
      (node (ref "SW8") (pin "3") (pinfunction "3_3") (pintype "passive"))
    )
    (net (code "50") (name "Net-(R9-Pad2)") (class "Default")
      (node (ref "R9") (pin "2") (pinfunction "2_2") (pintype "passive"))
      (node (ref "SW9") (pin "3") (pinfunction "3_3") (pintype "passive"))
    )
    (net (code "51") (name "Net-(R10-Pad2)") (class "Default")
      (node (ref "R10") (pin "2") (pinfunction "2_2") (pintype "passive"))
      (node (ref "SW10") (pin "3") (pinfunction "3_3") (pintype "passive"))
    )
    (net (code "52") (name "Net-(R11-Pad2)") (class "Default")
      (node (ref "R11") (pin "2") (pinfunction "2_2") (pintype "passive"))
      (node (ref "SW11") (pin "3") (pinfunction "3_3") (pintype "passive"))
    )
    (net (code "53") (name "Net-(R12-Pad2)") (class "Default")
      (node (ref "R12") (pin "2") (pinfunction "2_2") (pintype "passive"))
      (node (ref "SW12") (pin "3") (pinfunction "3_3") (pintype "passive"))
    )
    (net (code "54") (name "Net-(R13-Pad2)") (class "Default")
      (node (ref "R13") (pin "2") (pinfunction "2_2") (pintype "passive"))
      (node (ref "SW13") (pin "3") (pinfunction "3_3") (pintype "passive"))
    )
    (net (code "55") (name "Net-(R14-Pad2)") (class "Default")
      (node (ref "R14") (pin "2") (pinfunction "2_2") (pintype "passive"))
      (node (ref "SW14") (pin "3") (pinfunction "3_3") (pintype "passive"))
    )
    (net (code "56") (name "Net-(R15-Pad2)") (class "Default")
      (node (ref "R15") (pin "2") (pinfunction "2_2") (pintype "passive"))
      (node (ref "SW15") (pin "3") (pinfunction "3_3") (pintype "passive"))
    )
    (net (code "57") (name "Net-(R16-Pad2)") (class "Default")
      (node (ref "R16") (pin "2") (pinfunction "2_2") (pintype "passive"))
      (node (ref "SW16") (pin "3") (pinfunction "3_3") (pintype "passive"))
    )
    (net (code "58") (name "Net-(R17-Pad2)") (class "Default")
      (node (ref "R17") (pin "2") (pinfunction "2_2") (pintype "passive"))
      (node (ref "SW17") (pin "3") (pinfunction "3_3") (pintype "passive"))
    )
    (net (code "59") (name "Net-(R18-Pad2)") (class "Default")
      (node (ref "R18") (pin "2") (pinfunction "2_2") (pintype "passive"))
      (node (ref "SW18") (pin "3") (pinfunction "3_3") (pintype "passive"))
    )
    (net (code "60") (name "Net-(R19-Pad2)") (class "Default")
      (node (ref "R19") (pin "2") (pinfunction "2_2") (pintype "passive"))
      (node (ref "SW19") (pin "3") (pinfunction "3_3") (pintype "passive"))
    )
    (net (code "61") (name "Net-(R20-Pad2)") (class "Default")
      (node (ref "R20") (pin "2") (pinfunction "2_2") (pintype "passive"))
      (node (ref "SW20") (pin "3") (pinfunction "3_3") (pintype "passive"))
    )
    (net (code "62") (name "Net-(R21-Pad2)") (class "Default")
      (node (ref "R21") (pin "2") (pinfunction "2_2") (pintype "passive"))
      (node (ref "SW21") (pin "3") (pinfunction "3_3") (pintype "passive"))
    )
    (net (code "63") (name "Net-(R22-Pad2)") (class "Default")
      (node (ref "R22") (pin "2") (pinfunction "2_2") (pintype "passive"))
      (node (ref "SW22") (pin "3") (pinfunction "3_3") (pintype "passive"))
    )
    (net (code "64") (name "Net-(R23-Pad2)") (class "Default")
      (node (ref "R23") (pin "2") (pinfunction "2_2") (pintype "passive"))
      (node (ref "SW23") (pin "3") (pinfunction "3_3") (pintype "passive"))
    )
    (net (code "65") (name "Net-(R24-Pad2)") (class "Default")
      (node (ref "R24") (pin "2") (pinfunction "2_2") (pintype "passive"))
      (node (ref "SW24") (pin "3") (pinfunction "3_3") (pintype "passive"))
    )
    (net (code "66") (name "Net-(R25-Pad2)") (class "Default")
      (node (ref "R25") (pin "2") (pinfunction "2_2") (pintype "passive"))
      (node (ref "SW25") (pin "3") (pinfunction "3_3") (pintype "passive"))
    )
    (net (code "67") (name "Net-(R26-Pad2)") (class "Default")
      (node (ref "R26") (pin "2") (pinfunction "2_2") (pintype "passive"))
      (node (ref "SW26") (pin "3") (pinfunction "3_3") (pintype "passive"))
    )
    (net (code "68") (name "Net-(R27-Pad2)") (class "Default")
      (node (ref "R27") (pin "2") (pinfunction "2_2") (pintype "passive"))
      (node (ref "SW27") (pin "3") (pinfunction "3_3") (pintype "passive"))
    )
    (net (code "69") (name "Net-(R28-Pad2)") (class "Default")
      (node (ref "R28") (pin "2") (pinfunction "2_2") (pintype "passive"))
      (node (ref "SW28") (pin "3") (pinfunction "3_3") (pintype "passive"))
    )
    (net (code "70") (name "Net-(R29-Pad2)") (class "Default")
      (node (ref "R29") (pin "2") (pinfunction "2_2") (pintype "passive"))
      (node (ref "SW29") (pin "3") (pinfunction "3_3") (pintype "passive"))
    )
    (net (code "71") (name "Net-(R30-Pad2)") (class "Default")
      (node (ref "R30") (pin "2") (pinfunction "2_2") (pintype "passive"))
      (node (ref "SW30") (pin "3") (pinfunction "3_3") (pintype "passive"))
    )
    (net (code "72") (name "Net-(R31-Pad2)") (class "Default")
      (node (ref "R31") (pin "2") (pinfunction "2_2") (pintype "passive"))
      (node (ref "SW31") (pin "3") (pinfunction "3_3") (pintype "passive"))
    )
    (net (code "73") (name "Net-(R32-Pad2)") (class "Default")
      (node (ref "R32") (pin "2") (pinfunction "2_2") (pintype "passive"))
      (node (ref "SW32") (pin "3") (pinfunction "3_3") (pintype "passive"))
    )
    (net (code "74") (name "Net-(R33-Pad2)") (class "Default")
      (node (ref "R33") (pin "2") (pinfunction "2_2") (pintype "passive"))
      (node (ref "SW33") (pin "3") (pinfunction "3_3") (pintype "passive"))
    )
    (net (code "75") (name "Net-(R34-Pad2)") (class "Default")
      (node (ref "R34") (pin "2") (pinfunction "2_2") (pintype "passive"))
      (node (ref "SW34") (pin "3") (pinfunction "3_3") (pintype "passive"))
    )
    (net (code "76") (name "Net-(R35-Pad2)") (class "Default")
      (node (ref "R35") (pin "2") (pinfunction "2_2") (pintype "passive"))
      (node (ref "SW35") (pin "3") (pinfunction "3_3") (pintype "passive"))
    )
    (net (code "77") (name "Net-(R36-Pad2)") (class "Default")
      (node (ref "R36") (pin "2") (pinfunction "2_2") (pintype "passive"))
      (node (ref "SW36") (pin "3") (pinfunction "3_3") (pintype "passive"))
    )
    (net (code "78") (name "Net-(R37-Pad2)") (class "Default")
      (node (ref "R37") (pin "2") (pinfunction "2_2") (pintype "passive"))
      (node (ref "SW37") (pin "3") (pinfunction "3_3") (pintype "passive"))
    )
    (net (code "79") (name "Net-(R38-Pad2)") (class "Default")
      (node (ref "R38") (pin "2") (pinfunction "2_2") (pintype "passive"))
      (node (ref "SW38") (pin "3") (pinfunction "3_3") (pintype "passive"))
    )
    (net (code "80") (name "Net-(R39-Pad2)") (class "Default")
      (node (ref "R39") (pin "2") (pinfunction "2_2") (pintype "passive"))
      (node (ref "SW39") (pin "3") (pinfunction "3_3") (pintype "passive"))
    )
    (net (code "81") (name "Net-(R40-Pad2)") (class "Default")
      (node (ref "R40") (pin "2") (pinfunction "2_2") (pintype "passive"))
      (node (ref "SW40") (pin "3") (pinfunction "3_3") (pintype "passive"))
    )
    (net (code "82") (name "VCC") (class "Default")
      (node (ref "P2") (pin "1") (pinfunction "1_1") (pintype "passive"))
      (node (ref "R1") (pin "1") (pinfunction "1_1") (pintype "passive"))
      (node (ref "R10") (pin "1") (pinfunction "1_1") (pintype "passive"))
      (node (ref "R11") (pin "1") (pinfunction "1_1") (pintype "passive"))
      (node (ref "R12") (pin "1") (pinfunction "1_1") (pintype "passive"))
      (node (ref "R13") (pin "1") (pinfunction "1_1") (pintype "passive"))
      (node (ref "R14") (pin "1") (pinfunction "1_1") (pintype "passive"))
      (node (ref "R15") (pin "1") (pinfunction "1_1") (pintype "passive"))
      (node (ref "R16") (pin "1") (pinfunction "1_1") (pintype "passive"))
      (node (ref "R17") (pin "1") (pinfunction "1_1") (pintype "passive"))
      (node (ref "R18") (pin "1") (pinfunction "1_1") (pintype "passive"))
      (node (ref "R19") (pin "1") (pinfunction "1_1") (pintype "passive"))
      (node (ref "R2") (pin "1") (pinfunction "1_1") (pintype "passive"))
      (node (ref "R20") (pin "1") (pinfunction "1_1") (pintype "passive"))
      (node (ref "R21") (pin "1") (pinfunction "1_1") (pintype "passive"))
      (node (ref "R22") (pin "1") (pinfunction "1_1") (pintype "passive"))
      (node (ref "R23") (pin "1") (pinfunction "1_1") (pintype "passive"))
      (node (ref "R24") (pin "1") (pinfunction "1_1") (pintype "passive"))
      (node (ref "R25") (pin "1") (pinfunction "1_1") (pintype "passive"))
      (node (ref "R26") (pin "1") (pinfunction "1_1") (pintype "passive"))
      (node (ref "R27") (pin "1") (pinfunction "1_1") (pintype "passive"))
      (node (ref "R28") (pin "1") (pinfunction "1_1") (pintype "passive"))
      (node (ref "R29") (pin "1") (pinfunction "1_1") (pintype "passive"))
      (node (ref "R3") (pin "1") (pinfunction "1_1") (pintype "passive"))
      (node (ref "R30") (pin "1") (pinfunction "1_1") (pintype "passive"))
      (node (ref "R31") (pin "1") (pinfunction "1_1") (pintype "passive"))
      (node (ref "R32") (pin "1") (pinfunction "1_1") (pintype "passive"))
      (node (ref "R33") (pin "1") (pinfunction "1_1") (pintype "passive"))
      (node (ref "R34") (pin "1") (pinfunction "1_1") (pintype "passive"))
      (node (ref "R35") (pin "1") (pinfunction "1_1") (pintype "passive"))
      (node (ref "R36") (pin "1") (pinfunction "1_1") (pintype "passive"))
      (node (ref "R37") (pin "1") (pinfunction "1_1") (pintype "passive"))
      (node (ref "R38") (pin "1") (pinfunction "1_1") (pintype "passive"))
      (node (ref "R39") (pin "1") (pinfunction "1_1") (pintype "passive"))
      (node (ref "R4") (pin "1") (pinfunction "1_1") (pintype "passive"))
      (node (ref "R40") (pin "1") (pinfunction "1_1") (pintype "passive"))
      (node (ref "R5") (pin "1") (pinfunction "1_1") (pintype "passive"))
      (node (ref "R6") (pin "1") (pinfunction "1_1") (pintype "passive"))
      (node (ref "R7") (pin "1") (pinfunction "1_1") (pintype "passive"))
      (node (ref "R8") (pin "1") (pinfunction "1_1") (pintype "passive"))
      (node (ref "R9") (pin "1") (pinfunction "1_1") (pintype "passive"))
    )
  )
)
